# SWITCH.net
KiCad netlist of a schematic drawn in EAGLE
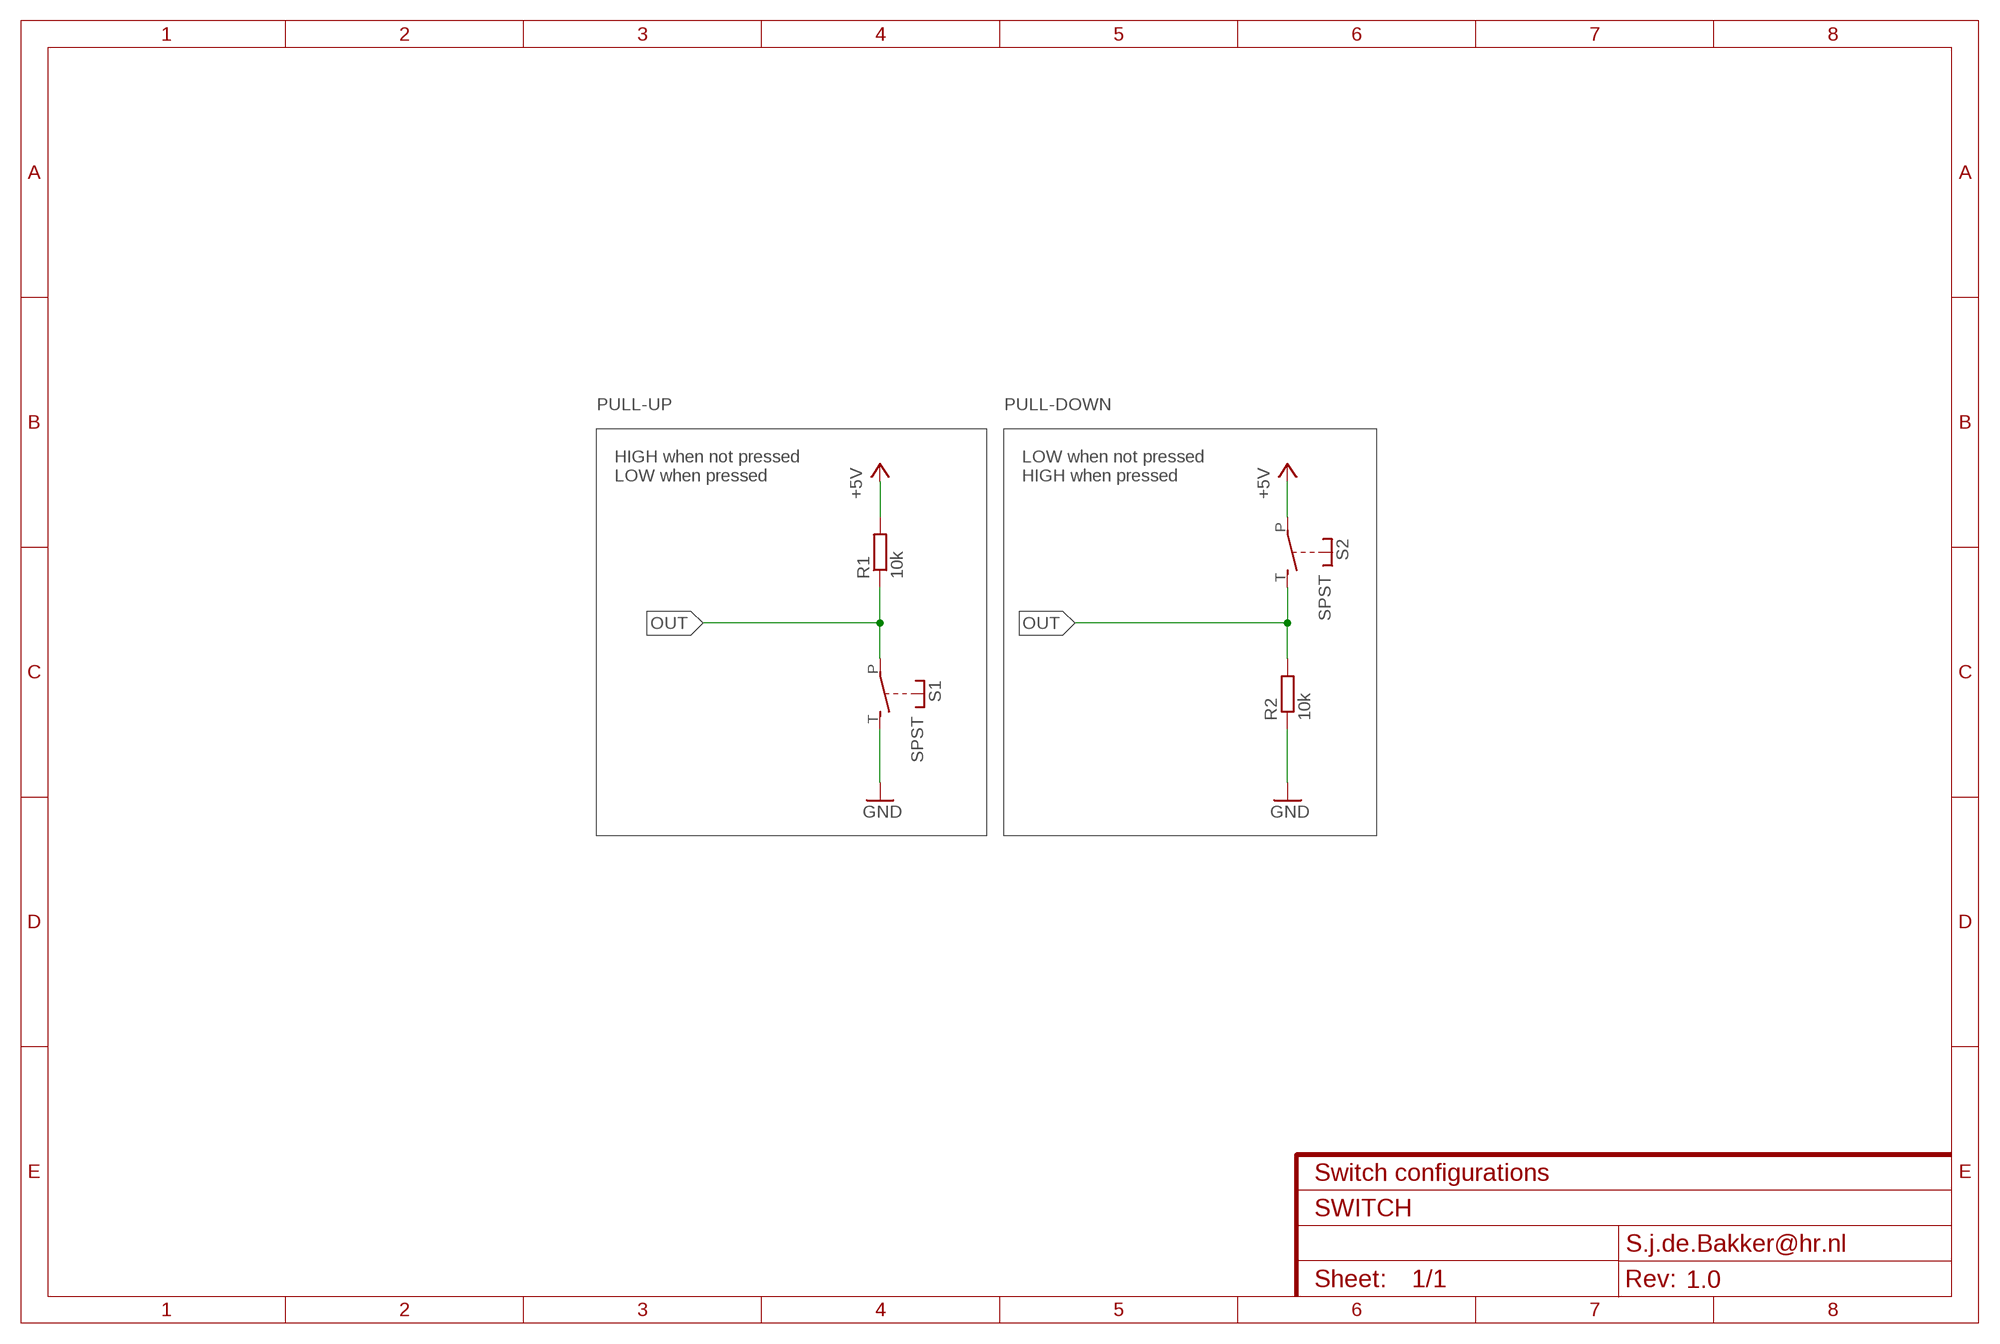
[diagram p0: schematic, sheet 1]

(export (version "E")
  (design (tool "Eeschema 10.0.6"))
  (components
    (comp (ref "R1")
      (value "10k")
      (footprint "eagle-import:R0603")
      (libsource (lib "eagle-import") (part "R-EU_R0603"))
    )
    (comp (ref "R2")
      (value "10k")
      (footprint "eagle-import:R0603")
      (libsource (lib "eagle-import") (part "R-EU_R0603"))
    )
    (comp (ref "S1")
      (value "SPST")
      (footprint "eagle-import:JUDCOSPST")
      (libsource (lib "eagle-import") (part "SPST"))
    )
    (comp (ref "S2")
      (value "SPST")
      (footprint "eagle-import:JUDCOSPST")
      (libsource (lib "eagle-import") (part "SPST"))
    )
  )
  (nets
    (net (code "1") (name "+5V") (class "Default")
      (node (ref "R1") (pin "2") (pinfunction "2_2") (pintype "passive"))
      (node (ref "S2") (pin "P") (pinfunction "P_P") (pintype "passive"))
    )
    (net (code "2") (name "GND") (class "Default")
      (node (ref "R2") (pin "1") (pinfunction "1_1") (pintype "passive"))
      (node (ref "S1") (pin "T") (pinfunction "S_T") (pintype "passive"))
    )
    (net (code "3") (name "OUT") (class "Default")
      (node (ref "R1") (pin "1") (pinfunction "1_1") (pintype "passive"))
      (node (ref "R2") (pin "2") (pinfunction "2_2") (pintype "passive"))
      (node (ref "S1") (pin "P") (pinfunction "P_P") (pintype "passive"))
      (node (ref "S2") (pin "T") (pinfunction "S_T") (pintype "passive"))
    )
  )
)
